# SensorSGP30.net
KiCad netlist of a schematic drawn in Altium Designer
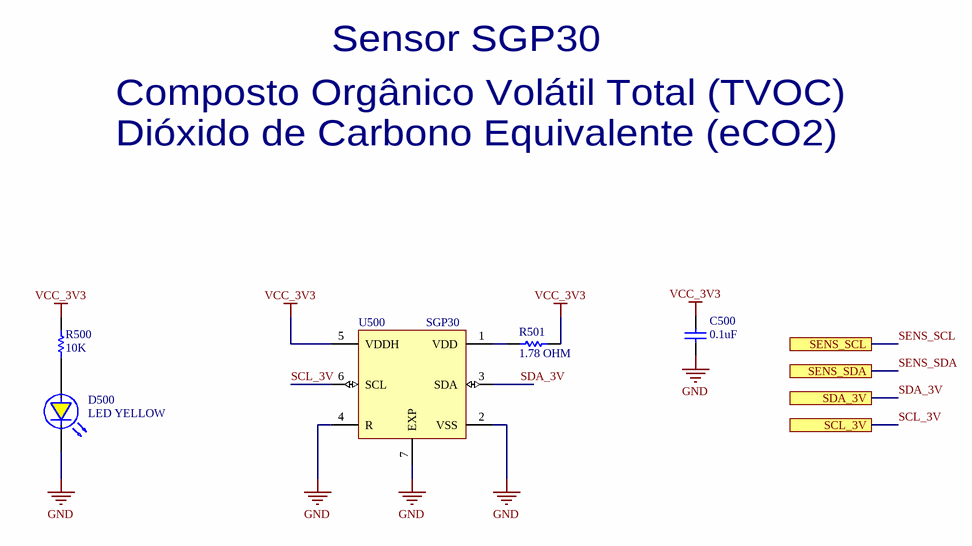
[diagram p0: SensorSGP30.SchDoc]

(export (version "E")
  (design (tool "Eeschema 10.0.6"))
  (components
    (comp (ref "C500")
      (value "0.1uF")
      (footprint "CAP_CER_0603")
      (libsource (lib "PCB_TCC") (part "CAP_CER_0.1uF_0603"))
    )
    (comp (ref "D500")
      (value "LED YELLOW")
      (footprint "LED_YELLOW_SMD_0603")
      (libsource (lib "PCB_TCC") (part "LED_YELLOW_SMD_0603"))
    )
    (comp (ref "R500") (value "10K") (footprint "RES_0603") (libsource (lib "PCB_TCC") (part "RES_10K_0603")))
    (comp (ref "R501")
      (value "1.78 OHM")
      (footprint "RES_0603")
      (libsource (lib "PCB_TCC") (part "RES_1.78OHM_0603"))
    )
    (comp (ref "U500") (value "SGP30") (footprint "SGP30") (libsource (lib "PCB_TCC") (part "SGP30")))
  )
  (nets
    (net (code "1") (name "/SCL_3V") (class "Default")
      (node (ref "U500") (pin "6") (pinfunction "SCL_6") (pintype "bidirectional"))
    )
    (net (code "2") (name "/SDA_3V") (class "Default")
      (node (ref "U500") (pin "3") (pinfunction "SDA_3") (pintype "bidirectional"))
    )
    (net (code "5") (name "GND") (class "Default")
      (node (ref "C500") (pin "1") (pinfunction "1_1") (pintype "passive"))
      (node (ref "D500") (pin "K") (pinfunction "K_K") (pintype "passive"))
      (node (ref "U500") (pin "2") (pinfunction "VSS_2") (pintype "power_in"))
      (node (ref "U500") (pin "4") (pinfunction "R_4") (pintype "passive"))
      (node (ref "U500") (pin "7") (pinfunction "EXP_7") (pintype "power_in"))
    )
    (net (code "6") (name "Net-(D500-PadA)") (class "Default")
      (node (ref "D500") (pin "A") (pinfunction "A_A") (pintype "passive"))
      (node (ref "R500") (pin "1") (pinfunction "1_1") (pintype "passive"))
    )
    (net (code "7") (name "Net-(U500-VDD)") (class "Default")
      (node (ref "R501") (pin "1") (pinfunction "1_1") (pintype "passive"))
      (node (ref "U500") (pin "1") (pinfunction "VDD_1") (pintype "power_in"))
    )
    (net (code "8") (name "VCC_3V3") (class "Default")
      (node (ref "C500") (pin "2") (pinfunction "2_2") (pintype "passive"))
      (node (ref "R500") (pin "2") (pinfunction "2_2") (pintype "passive"))
      (node (ref "R501") (pin "2") (pinfunction "2_2") (pintype "passive"))
      (node (ref "U500") (pin "5") (pinfunction "VDDH_5") (pintype "power_in"))
    )
  )
)
